# House_LED_Replace_WS5050.net
KiCad netlist of a schematic drawn in EAGLE
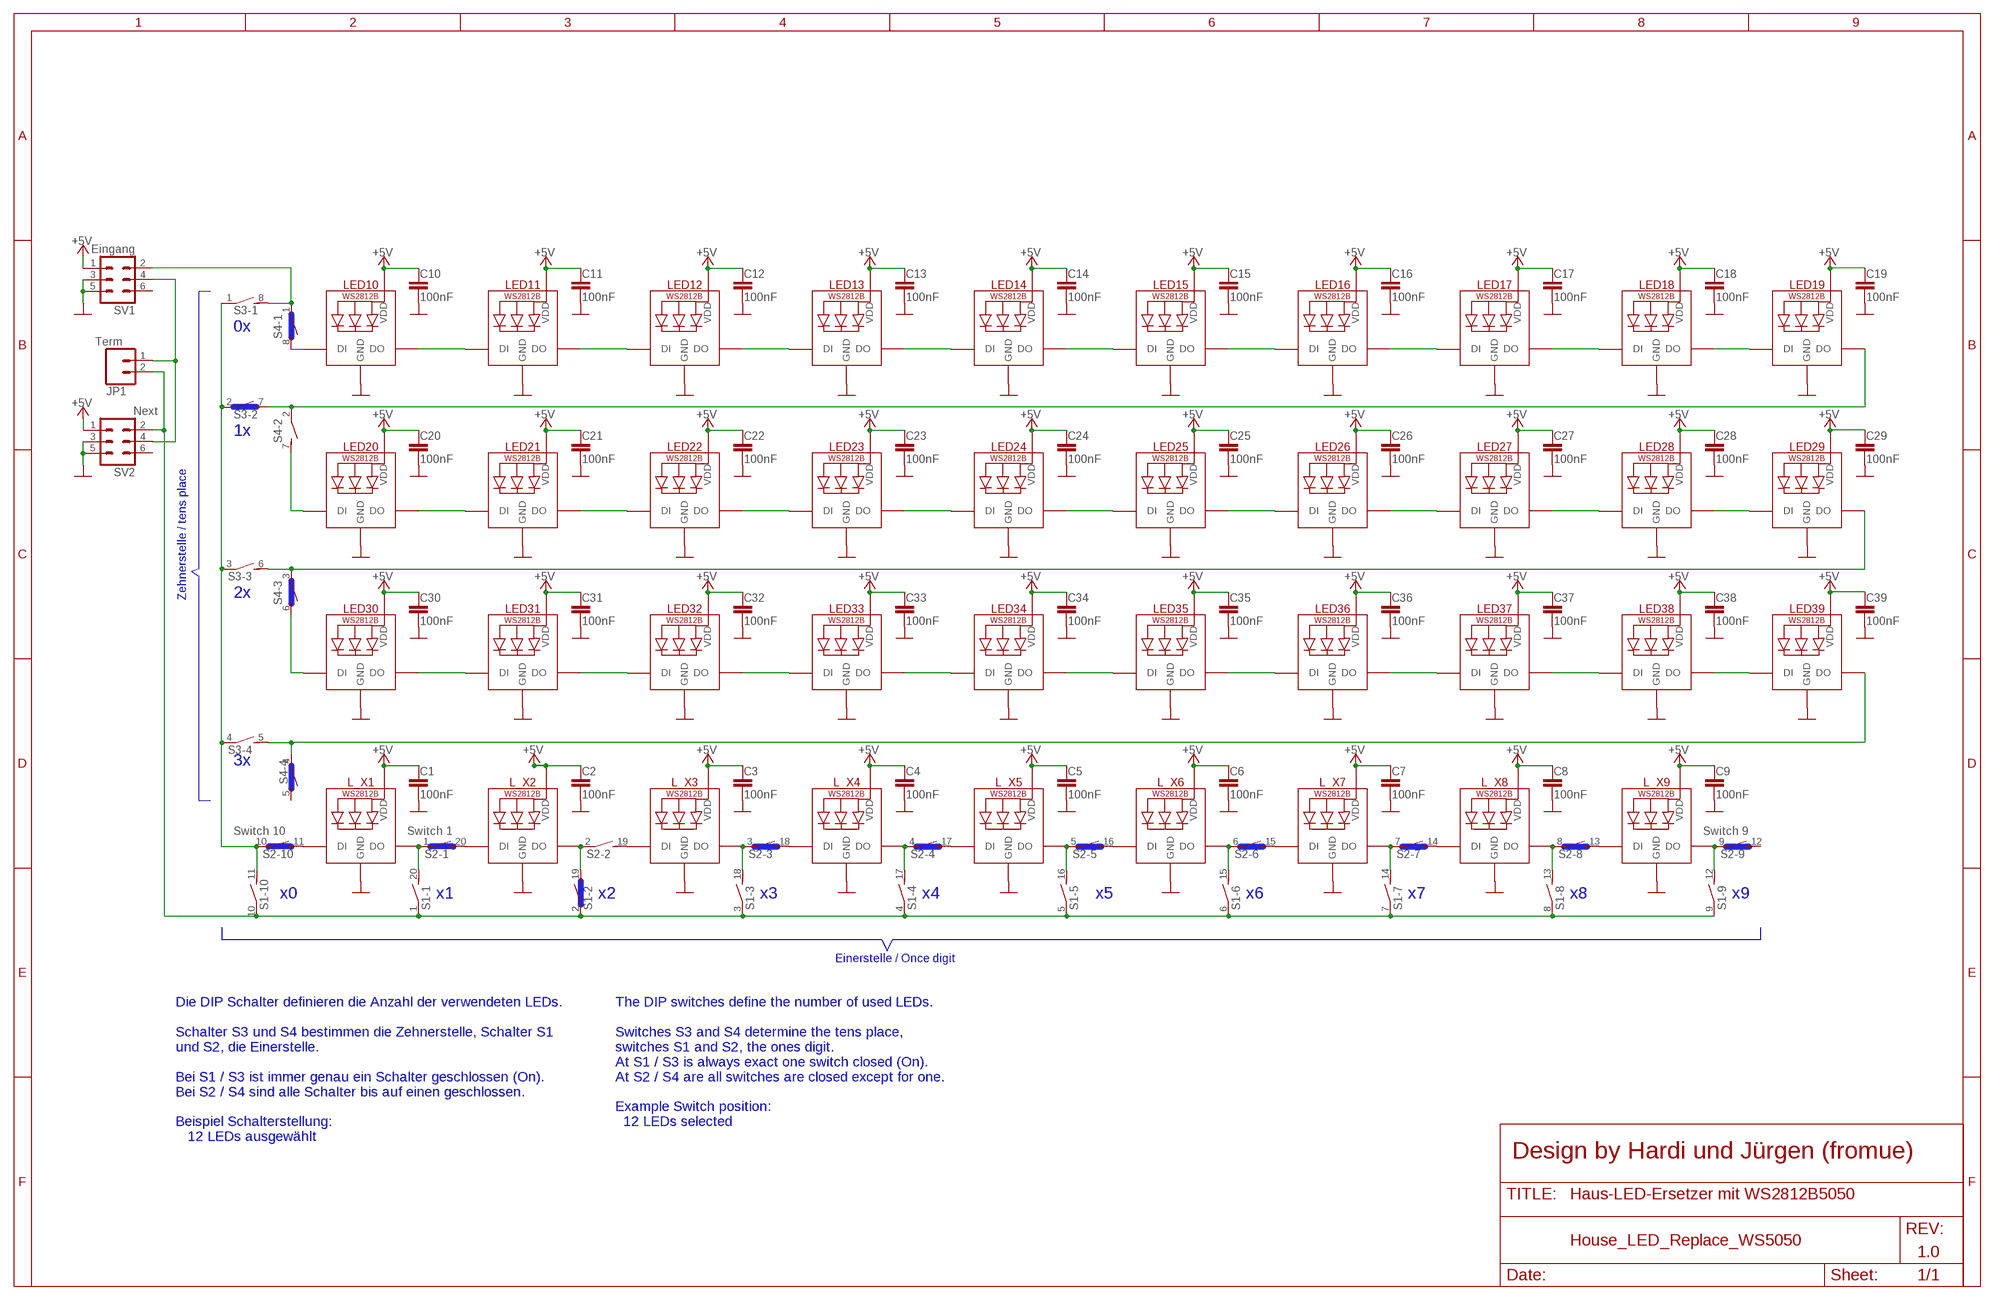
[diagram p0: schematic, sheet 1]

(export (version "E")
  (design (tool "Eeschema 10.0.6"))
  (components
    (comp (ref "C1")
      (value "100nF")
      (footprint "eagle-import:C0603")
      (libsource (lib "eagle-import") (part "C-EUC0603"))
    )
    (comp (ref "C2")
      (value "100nF")
      (footprint "eagle-import:C0603")
      (libsource (lib "eagle-import") (part "C-EUC0603"))
    )
    (comp (ref "C3")
      (value "100nF")
      (footprint "eagle-import:C0603")
      (libsource (lib "eagle-import") (part "C-EUC0603"))
    )
    (comp (ref "C4")
      (value "100nF")
      (footprint "eagle-import:C0603")
      (libsource (lib "eagle-import") (part "C-EUC0603"))
    )
    (comp (ref "C5")
      (value "100nF")
      (footprint "eagle-import:C0603")
      (libsource (lib "eagle-import") (part "C-EUC0603"))
    )
    (comp (ref "C6")
      (value "100nF")
      (footprint "eagle-import:C0603")
      (libsource (lib "eagle-import") (part "C-EUC0603"))
    )
    (comp (ref "C7")
      (value "100nF")
      (footprint "eagle-import:C0603")
      (libsource (lib "eagle-import") (part "C-EUC0603"))
    )
    (comp (ref "C8")
      (value "100nF")
      (footprint "eagle-import:C0603")
      (libsource (lib "eagle-import") (part "C-EUC0603"))
    )
    (comp (ref "C9")
      (value "100nF")
      (footprint "eagle-import:C0603")
      (libsource (lib "eagle-import") (part "C-EUC0603"))
    )
    (comp (ref "C10")
      (value "100nF")
      (footprint "eagle-import:C0603")
      (libsource (lib "eagle-import") (part "C-EUC0603"))
    )
    (comp (ref "C11")
      (value "100nF")
      (footprint "eagle-import:C0603")
      (libsource (lib "eagle-import") (part "C-EUC0603"))
    )
    (comp (ref "C12")
      (value "100nF")
      (footprint "eagle-import:C0603")
      (libsource (lib "eagle-import") (part "C-EUC0603"))
    )
    (comp (ref "C13")
      (value "100nF")
      (footprint "eagle-import:C0603")
      (libsource (lib "eagle-import") (part "C-EUC0603"))
    )
    (comp (ref "C14")
      (value "100nF")
      (footprint "eagle-import:C0603")
      (libsource (lib "eagle-import") (part "C-EUC0603"))
    )
    (comp (ref "C15")
      (value "100nF")
      (footprint "eagle-import:C0603")
      (libsource (lib "eagle-import") (part "C-EUC0603"))
    )
    (comp (ref "C16")
      (value "100nF")
      (footprint "eagle-import:C0603")
      (libsource (lib "eagle-import") (part "C-EUC0603"))
    )
    (comp (ref "C17")
      (value "100nF")
      (footprint "eagle-import:C0603")
      (libsource (lib "eagle-import") (part "C-EUC0603"))
    )
    (comp (ref "C18")
      (value "100nF")
      (footprint "eagle-import:C0603")
      (libsource (lib "eagle-import") (part "C-EUC0603"))
    )
    (comp (ref "C19")
      (value "100nF")
      (footprint "eagle-import:C0603")
      (libsource (lib "eagle-import") (part "C-EUC0603"))
    )
    (comp (ref "C20")
      (value "100nF")
      (footprint "eagle-import:C0603")
      (libsource (lib "eagle-import") (part "C-EUC0603"))
    )
    (comp (ref "C21")
      (value "100nF")
      (footprint "eagle-import:C0603")
      (libsource (lib "eagle-import") (part "C-EUC0603"))
    )
    (comp (ref "C22")
      (value "100nF")
      (footprint "eagle-import:C0603")
      (libsource (lib "eagle-import") (part "C-EUC0603"))
    )
    (comp (ref "C23")
      (value "100nF")
      (footprint "eagle-import:C0603")
      (libsource (lib "eagle-import") (part "C-EUC0603"))
    )
    (comp (ref "C24")
      (value "100nF")
      (footprint "eagle-import:C0603")
      (libsource (lib "eagle-import") (part "C-EUC0603"))
    )
    (comp (ref "C25")
      (value "100nF")
      (footprint "eagle-import:C0603")
      (libsource (lib "eagle-import") (part "C-EUC0603"))
    )
    (comp (ref "C26")
      (value "100nF")
      (footprint "eagle-import:C0603")
      (libsource (lib "eagle-import") (part "C-EUC0603"))
    )
    (comp (ref "C27")
      (value "100nF")
      (footprint "eagle-import:C0603")
      (libsource (lib "eagle-import") (part "C-EUC0603"))
    )
    (comp (ref "C28")
      (value "100nF")
      (footprint "eagle-import:C0603")
      (libsource (lib "eagle-import") (part "C-EUC0603"))
    )
    (comp (ref "C29")
      (value "100nF")
      (footprint "eagle-import:C0603")
      (libsource (lib "eagle-import") (part "C-EUC0603"))
    )
    (comp (ref "C30")
      (value "100nF")
      (footprint "eagle-import:C0603")
      (libsource (lib "eagle-import") (part "C-EUC0603"))
    )
    (comp (ref "C31")
      (value "100nF")
      (footprint "eagle-import:C0603")
      (libsource (lib "eagle-import") (part "C-EUC0603"))
    )
    (comp (ref "C32")
      (value "100nF")
      (footprint "eagle-import:C0603")
      (libsource (lib "eagle-import") (part "C-EUC0603"))
    )
    (comp (ref "C33")
      (value "100nF")
      (footprint "eagle-import:C0603")
      (libsource (lib "eagle-import") (part "C-EUC0603"))
    )
    (comp (ref "C34")
      (value "100nF")
      (footprint "eagle-import:C0603")
      (libsource (lib "eagle-import") (part "C-EUC0603"))
    )
    (comp (ref "C35")
      (value "100nF")
      (footprint "eagle-import:C0603")
      (libsource (lib "eagle-import") (part "C-EUC0603"))
    )
    (comp (ref "C36")
      (value "100nF")
      (footprint "eagle-import:C0603")
      (libsource (lib "eagle-import") (part "C-EUC0603"))
    )
    (comp (ref "C37")
      (value "100nF")
      (footprint "eagle-import:C0603")
      (libsource (lib "eagle-import") (part "C-EUC0603"))
    )
    (comp (ref "C38")
      (value "100nF")
      (footprint "eagle-import:C0603")
      (libsource (lib "eagle-import") (part "C-EUC0603"))
    )
    (comp (ref "C39")
      (value "100nF")
      (footprint "eagle-import:C0603")
      (libsource (lib "eagle-import") (part "C-EUC0603"))
    )
    (comp (ref "JP1")
      (value "Term")
      (footprint "eagle-import:1X02")
      (libsource (lib "eagle-import") (part "M02PTH"))
    )
    (comp (ref "LED10")
      (value "WS2812B5050")
      (footprint "eagle-import:WS2812B")
      (libsource (lib "eagle-import") (part "WS2812B5050"))
    )
    (comp (ref "LED11")
      (value "WS2812B5050")
      (footprint "eagle-import:WS2812B")
      (libsource (lib "eagle-import") (part "WS2812B5050"))
    )
    (comp (ref "LED12")
      (value "WS2812B5050")
      (footprint "eagle-import:WS2812B")
      (libsource (lib "eagle-import") (part "WS2812B5050"))
    )
    (comp (ref "LED13")
      (value "WS2812B5050")
      (footprint "eagle-import:WS2812B")
      (libsource (lib "eagle-import") (part "WS2812B5050"))
    )
    (comp (ref "LED14")
      (value "WS2812B5050")
      (footprint "eagle-import:WS2812B")
      (libsource (lib "eagle-import") (part "WS2812B5050"))
    )
    (comp (ref "LED15")
      (value "WS2812B5050")
      (footprint "eagle-import:WS2812B")
      (libsource (lib "eagle-import") (part "WS2812B5050"))
    )
    (comp (ref "LED16")
      (value "WS2812B5050")
      (footprint "eagle-import:WS2812B")
      (libsource (lib "eagle-import") (part "WS2812B5050"))
    )
    (comp (ref "LED17")
      (value "WS2812B5050")
      (footprint "eagle-import:WS2812B")
      (libsource (lib "eagle-import") (part "WS2812B5050"))
    )
    (comp (ref "LED18")
      (value "WS2812B5050")
      (footprint "eagle-import:WS2812B")
      (libsource (lib "eagle-import") (part "WS2812B5050"))
    )
    (comp (ref "LED19")
      (value "WS2812B5050")
      (footprint "eagle-import:WS2812B")
      (libsource (lib "eagle-import") (part "WS2812B5050"))
    )
    (comp (ref "LED20")
      (value "WS2812B5050")
      (footprint "eagle-import:WS2812B")
      (libsource (lib "eagle-import") (part "WS2812B5050"))
    )
    (comp (ref "LED21")
      (value "WS2812B5050")
      (footprint "eagle-import:WS2812B")
      (libsource (lib "eagle-import") (part "WS2812B5050"))
    )
    (comp (ref "LED22")
      (value "WS2812B5050")
      (footprint "eagle-import:WS2812B")
      (libsource (lib "eagle-import") (part "WS2812B5050"))
    )
    (comp (ref "LED23")
      (value "WS2812B5050")
      (footprint "eagle-import:WS2812B")
      (libsource (lib "eagle-import") (part "WS2812B5050"))
    )
    (comp (ref "LED24")
      (value "WS2812B5050")
      (footprint "eagle-import:WS2812B")
      (libsource (lib "eagle-import") (part "WS2812B5050"))
    )
    (comp (ref "LED25")
      (value "WS2812B5050")
      (footprint "eagle-import:WS2812B")
      (libsource (lib "eagle-import") (part "WS2812B5050"))
    )
    (comp (ref "LED26")
      (value "WS2812B5050")
      (footprint "eagle-import:WS2812B")
      (libsource (lib "eagle-import") (part "WS2812B5050"))
    )
    (comp (ref "LED27")
      (value "WS2812B5050")
      (footprint "eagle-import:WS2812B")
      (libsource (lib "eagle-import") (part "WS2812B5050"))
    )
    (comp (ref "LED28")
      (value "WS2812B5050")
      (footprint "eagle-import:WS2812B")
      (libsource (lib "eagle-import") (part "WS2812B5050"))
    )
    (comp (ref "LED29")
      (value "WS2812B5050")
      (footprint "eagle-import:WS2812B")
      (libsource (lib "eagle-import") (part "WS2812B5050"))
    )
    (comp (ref "LED30")
      (value "WS2812B5050")
      (footprint "eagle-import:WS2812B")
      (libsource (lib "eagle-import") (part "WS2812B5050"))
    )
    (comp (ref "LED31")
      (value "WS2812B5050")
      (footprint "eagle-import:WS2812B")
      (libsource (lib "eagle-import") (part "WS2812B5050"))
    )
    (comp (ref "LED32")
      (value "WS2812B5050")
      (footprint "eagle-import:WS2812B")
      (libsource (lib "eagle-import") (part "WS2812B5050"))
    )
    (comp (ref "LED33")
      (value "WS2812B5050")
      (footprint "eagle-import:WS2812B")
      (libsource (lib "eagle-import") (part "WS2812B5050"))
    )
    (comp (ref "LED34")
      (value "WS2812B5050")
      (footprint "eagle-import:WS2812B")
      (libsource (lib "eagle-import") (part "WS2812B5050"))
    )
    (comp (ref "LED35")
      (value "WS2812B5050")
      (footprint "eagle-import:WS2812B")
      (libsource (lib "eagle-import") (part "WS2812B5050"))
    )
    (comp (ref "LED36")
      (value "WS2812B5050")
      (footprint "eagle-import:WS2812B")
      (libsource (lib "eagle-import") (part "WS2812B5050"))
    )
    (comp (ref "LED37")
      (value "WS2812B5050")
      (footprint "eagle-import:WS2812B")
      (libsource (lib "eagle-import") (part "WS2812B5050"))
    )
    (comp (ref "LED38")
      (value "WS2812B5050")
      (footprint "eagle-import:WS2812B")
      (libsource (lib "eagle-import") (part "WS2812B5050"))
    )
    (comp (ref "LED39")
      (value "WS2812B5050")
      (footprint "eagle-import:WS2812B")
      (libsource (lib "eagle-import") (part "WS2812B5050"))
    )
    (comp (ref "L_X1")
      (value "WS2812B5050")
      (footprint "eagle-import:WS2812B")
      (libsource (lib "eagle-import") (part "WS2812B5050"))
    )
    (comp (ref "L_X2")
      (value "WS2812B5050")
      (footprint "eagle-import:WS2812B")
      (libsource (lib "eagle-import") (part "WS2812B5050"))
    )
    (comp (ref "L_X3")
      (value "WS2812B5050")
      (footprint "eagle-import:WS2812B")
      (libsource (lib "eagle-import") (part "WS2812B5050"))
    )
    (comp (ref "L_X4")
      (value "WS2812B5050")
      (footprint "eagle-import:WS2812B")
      (libsource (lib "eagle-import") (part "WS2812B5050"))
    )
    (comp (ref "L_X5")
      (value "WS2812B5050")
      (footprint "eagle-import:WS2812B")
      (libsource (lib "eagle-import") (part "WS2812B5050"))
    )
    (comp (ref "L_X6")
      (value "WS2812B5050")
      (footprint "eagle-import:WS2812B")
      (libsource (lib "eagle-import") (part "WS2812B5050"))
    )
    (comp (ref "L_X7")
      (value "WS2812B5050")
      (footprint "eagle-import:WS2812B")
      (libsource (lib "eagle-import") (part "WS2812B5050"))
    )
    (comp (ref "L_X8")
      (value "WS2812B5050")
      (footprint "eagle-import:WS2812B")
      (libsource (lib "eagle-import") (part "WS2812B5050"))
    )
    (comp (ref "L_X9")
      (value "WS2812B5050")
      (footprint "eagle-import:WS2812B")
      (libsource (lib "eagle-import") (part "WS2812B5050"))
    )
    (comp (ref "S1")
      (value "DIP10SB")
      (footprint "eagle-import:DIP10SB")
      (libsource (lib "eagle-import") (part "DIP10SB"))
    )
    (comp (ref "S2")
      (value "DIP10SB")
      (footprint "eagle-import:DIP10SB")
      (libsource (lib "eagle-import") (part "DIP10SB"))
    )
    (comp (ref "S3")
      (value "DIP04S")
      (footprint "eagle-import:DIP04S")
      (libsource (lib "eagle-import") (part "DIP04S"))
    )
    (comp (ref "S4")
      (value "DIP04S")
      (footprint "eagle-import:DIP04S")
      (libsource (lib "eagle-import") (part "DIP04S"))
    )
    (comp (ref "SV1")
      (value "Eingang")
      (footprint "eagle-import:ML6")
      (libsource (lib "eagle-import") (part "ML6"))
    )
    (comp (ref "SV2")
      (value "Next")
      (footprint "eagle-import:ML6")
      (libsource (lib "eagle-import") (part "ML6"))
    )
  )
  (nets
    (net (code "1") (name "+5V") (class "Default")
      (node (ref "C1") (pin "1") (pinfunction "1_1") (pintype "passive"))
      (node (ref "C10") (pin "1") (pinfunction "1_1") (pintype "passive"))
      (node (ref "C11") (pin "1") (pinfunction "1_1") (pintype "passive"))
      (node (ref "C12") (pin "1") (pinfunction "1_1") (pintype "passive"))
      (node (ref "C13") (pin "1") (pinfunction "1_1") (pintype "passive"))
      (node (ref "C14") (pin "1") (pinfunction "1_1") (pintype "passive"))
      (node (ref "C15") (pin "1") (pinfunction "1_1") (pintype "passive"))
      (node (ref "C16") (pin "1") (pinfunction "1_1") (pintype "passive"))
      (node (ref "C17") (pin "1") (pinfunction "1_1") (pintype "passive"))
      (node (ref "C18") (pin "1") (pinfunction "1_1") (pintype "passive"))
      (node (ref "C19") (pin "1") (pinfunction "1_1") (pintype "passive"))
      (node (ref "C2") (pin "1") (pinfunction "1_1") (pintype "passive"))
      (node (ref "C20") (pin "1") (pinfunction "1_1") (pintype "passive"))
      (node (ref "C21") (pin "1") (pinfunction "1_1") (pintype "passive"))
      (node (ref "C22") (pin "1") (pinfunction "1_1") (pintype "passive"))
      (node (ref "C23") (pin "1") (pinfunction "1_1") (pintype "passive"))
      (node (ref "C24") (pin "1") (pinfunction "1_1") (pintype "passive"))
      (node (ref "C25") (pin "1") (pinfunction "1_1") (pintype "passive"))
      (node (ref "C26") (pin "1") (pinfunction "1_1") (pintype "passive"))
      (node (ref "C27") (pin "1") (pinfunction "1_1") (pintype "passive"))
      (node (ref "C28") (pin "1") (pinfunction "1_1") (pintype "passive"))
      (node (ref "C29") (pin "1") (pinfunction "1_1") (pintype "passive"))
      (node (ref "C3") (pin "1") (pinfunction "1_1") (pintype "passive"))
      (node (ref "C30") (pin "1") (pinfunction "1_1") (pintype "passive"))
      (node (ref "C31") (pin "1") (pinfunction "1_1") (pintype "passive"))
      (node (ref "C32") (pin "1") (pinfunction "1_1") (pintype "passive"))
      (node (ref "C33") (pin "1") (pinfunction "1_1") (pintype "passive"))
      (node (ref "C34") (pin "1") (pinfunction "1_1") (pintype "passive"))
      (node (ref "C35") (pin "1") (pinfunction "1_1") (pintype "passive"))
      (node (ref "C36") (pin "1") (pinfunction "1_1") (pintype "passive"))
      (node (ref "C37") (pin "1") (pinfunction "1_1") (pintype "passive"))
      (node (ref "C38") (pin "1") (pinfunction "1_1") (pintype "passive"))
      (node (ref "C39") (pin "1") (pinfunction "1_1") (pintype "passive"))
      (node (ref "C4") (pin "1") (pinfunction "1_1") (pintype "passive"))
      (node (ref "C5") (pin "1") (pinfunction "1_1") (pintype "passive"))
      (node (ref "C6") (pin "1") (pinfunction "1_1") (pintype "passive"))
      (node (ref "C7") (pin "1") (pinfunction "1_1") (pintype "passive"))
      (node (ref "C8") (pin "1") (pinfunction "1_1") (pintype "passive"))
      (node (ref "C9") (pin "1") (pinfunction "1_1") (pintype "passive"))
      (node (ref "LED10") (pin "1-5V") (pinfunction "VDD_1-5V") (pintype "power_in"))
      (node (ref "LED11") (pin "1-5V") (pinfunction "VDD_1-5V") (pintype "power_in"))
      (node (ref "LED12") (pin "1-5V") (pinfunction "VDD_1-5V") (pintype "power_in"))
      (node (ref "LED13") (pin "1-5V") (pinfunction "VDD_1-5V") (pintype "power_in"))
      (node (ref "LED14") (pin "1-5V") (pinfunction "VDD_1-5V") (pintype "power_in"))
      (node (ref "LED15") (pin "1-5V") (pinfunction "VDD_1-5V") (pintype "power_in"))
      (node (ref "LED16") (pin "1-5V") (pinfunction "VDD_1-5V") (pintype "power_in"))
      (node (ref "LED17") (pin "1-5V") (pinfunction "VDD_1-5V") (pintype "power_in"))
      (node (ref "LED18") (pin "1-5V") (pinfunction "VDD_1-5V") (pintype "power_in"))
      (node (ref "LED19") (pin "1-5V") (pinfunction "VDD_1-5V") (pintype "power_in"))
      (node (ref "LED20") (pin "1-5V") (pinfunction "VDD_1-5V") (pintype "power_in"))
      (node (ref "LED21") (pin "1-5V") (pinfunction "VDD_1-5V") (pintype "power_in"))
      (node (ref "LED22") (pin "1-5V") (pinfunction "VDD_1-5V") (pintype "power_in"))
      (node (ref "LED23") (pin "1-5V") (pinfunction "VDD_1-5V") (pintype "power_in"))
      (node (ref "LED24") (pin "1-5V") (pinfunction "VDD_1-5V") (pintype "power_in"))
      (node (ref "LED25") (pin "1-5V") (pinfunction "VDD_1-5V") (pintype "power_in"))
      (node (ref "LED26") (pin "1-5V") (pinfunction "VDD_1-5V") (pintype "power_in"))
      (node (ref "LED27") (pin "1-5V") (pinfunction "VDD_1-5V") (pintype "power_in"))
      (node (ref "LED28") (pin "1-5V") (pinfunction "VDD_1-5V") (pintype "power_in"))
      (node (ref "LED29") (pin "1-5V") (pinfunction "VDD_1-5V") (pintype "power_in"))
      (node (ref "LED30") (pin "1-5V") (pinfunction "VDD_1-5V") (pintype "power_in"))
      (node (ref "LED31") (pin "1-5V") (pinfunction "VDD_1-5V") (pintype "power_in"))
      (node (ref "LED32") (pin "1-5V") (pinfunction "VDD_1-5V") (pintype "power_in"))
      (node (ref "LED33") (pin "1-5V") (pinfunction "VDD_1-5V") (pintype "power_in"))
      (node (ref "LED34") (pin "1-5V") (pinfunction "VDD_1-5V") (pintype "power_in"))
      (node (ref "LED35") (pin "1-5V") (pinfunction "VDD_1-5V") (pintype "power_in"))
      (node (ref "LED36") (pin "1-5V") (pinfunction "VDD_1-5V") (pintype "power_in"))
      (node (ref "LED37") (pin "1-5V") (pinfunction "VDD_1-5V") (pintype "power_in"))
      (node (ref "LED38") (pin "1-5V") (pinfunction "VDD_1-5V") (pintype "power_in"))
      (node (ref "LED39") (pin "1-5V") (pinfunction "VDD_1-5V") (pintype "power_in"))
      (node (ref "L_X1") (pin "1-5V") (pinfunction "VDD_1-5V") (pintype "power_in"))
      (node (ref "L_X2") (pin "1-5V") (pinfunction "VDD_1-5V") (pintype "power_in"))
      (node (ref "L_X3") (pin "1-5V") (pinfunction "VDD_1-5V") (pintype "power_in"))
      (node (ref "L_X4") (pin "1-5V") (pinfunction "VDD_1-5V") (pintype "power_in"))
      (node (ref "L_X5") (pin "1-5V") (pinfunction "VDD_1-5V") (pintype "power_in"))
      (node (ref "L_X6") (pin "1-5V") (pinfunction "VDD_1-5V") (pintype "power_in"))
      (node (ref "L_X7") (pin "1-5V") (pinfunction "VDD_1-5V") (pintype "power_in"))
      (node (ref "L_X8") (pin "1-5V") (pinfunction "VDD_1-5V") (pintype "power_in"))
      (node (ref "L_X9") (pin "1-5V") (pinfunction "VDD_1-5V") (pintype "power_in"))
      (node (ref "SV1") (pin "1") (pinfunction "1_1") (pintype "passive"))
      (node (ref "SV2") (pin "1") (pinfunction "1_1") (pintype "passive"))
    )
    (net (code "2") (name "GND") (class "Default")
      (node (ref "C1") (pin "2") (pinfunction "2_2") (pintype "passive"))
      (node (ref "C10") (pin "2") (pinfunction "2_2") (pintype "passive"))
      (node (ref "C11") (pin "2") (pinfunction "2_2") (pintype "passive"))
      (node (ref "C12") (pin "2") (pinfunction "2_2") (pintype "passive"))
      (node (ref "C13") (pin "2") (pinfunction "2_2") (pintype "passive"))
      (node (ref "C14") (pin "2") (pinfunction "2_2") (pintype "passive"))
      (node (ref "C15") (pin "2") (pinfunction "2_2") (pintype "passive"))
      (node (ref "C16") (pin "2") (pinfunction "2_2") (pintype "passive"))
      (node (ref "C17") (pin "2") (pinfunction "2_2") (pintype "passive"))
      (node (ref "C18") (pin "2") (pinfunction "2_2") (pintype "passive"))
      (node (ref "C19") (pin "2") (pinfunction "2_2") (pintype "passive"))
      (node (ref "C2") (pin "2") (pinfunction "2_2") (pintype "passive"))
      (node (ref "C20") (pin "2") (pinfunction "2_2") (pintype "passive"))
      (node (ref "C21") (pin "2") (pinfunction "2_2") (pintype "passive"))
      (node (ref "C22") (pin "2") (pinfunction "2_2") (pintype "passive"))
      (node (ref "C23") (pin "2") (pinfunction "2_2") (pintype "passive"))
      (node (ref "C24") (pin "2") (pinfunction "2_2") (pintype "passive"))
      (node (ref "C25") (pin "2") (pinfunction "2_2") (pintype "passive"))
      (node (ref "C26") (pin "2") (pinfunction "2_2") (pintype "passive"))
      (node (ref "C27") (pin "2") (pinfunction "2_2") (pintype "passive"))
      (node (ref "C28") (pin "2") (pinfunction "2_2") (pintype "passive"))
      (node (ref "C29") (pin "2") (pinfunction "2_2") (pintype "passive"))
      (node (ref "C3") (pin "2") (pinfunction "2_2") (pintype "passive"))
      (node (ref "C30") (pin "2") (pinfunction "2_2") (pintype "passive"))
      (node (ref "C31") (pin "2") (pinfunction "2_2") (pintype "passive"))
      (node (ref "C32") (pin "2") (pinfunction "2_2") (pintype "passive"))
      (node (ref "C33") (pin "2") (pinfunction "2_2") (pintype "passive"))
      (node (ref "C34") (pin "2") (pinfunction "2_2") (pintype "passive"))
      (node (ref "C35") (pin "2") (pinfunction "2_2") (pintype "passive"))
      (node (ref "C36") (pin "2") (pinfunction "2_2") (pintype "passive"))
      (node (ref "C37") (pin "2") (pinfunction "2_2") (pintype "passive"))
      (node (ref "C38") (pin "2") (pinfunction "2_2") (pintype "passive"))
      (node (ref "C39") (pin "2") (pinfunction "2_2") (pintype "passive"))
      (node (ref "C4") (pin "2") (pinfunction "2_2") (pintype "passive"))
      (node (ref "C5") (pin "2") (pinfunction "2_2") (pintype "passive"))
      (node (ref "C6") (pin "2") (pinfunction "2_2") (pintype "passive"))
      (node (ref "C7") (pin "2") (pinfunction "2_2") (pintype "passive"))
      (node (ref "C8") (pin "2") (pinfunction "2_2") (pintype "passive"))
      (node (ref "C9") (pin "2") (pinfunction "2_2") (pintype "passive"))
      (node (ref "LED10") (pin "3-GND") (pinfunction "GND_3-GND") (pintype "power_in"))
      (node (ref "LED11") (pin "3-GND") (pinfunction "GND_3-GND") (pintype "power_in"))
      (node (ref "LED12") (pin "3-GND") (pinfunction "GND_3-GND") (pintype "power_in"))
      (node (ref "LED13") (pin "3-GND") (pinfunction "GND_3-GND") (pintype "power_in"))
      (node (ref "LED14") (pin "3-GND") (pinfunction "GND_3-GND") (pintype "power_in"))
      (node (ref "LED15") (pin "3-GND") (pinfunction "GND_3-GND") (pintype "power_in"))
      (node (ref "LED16") (pin "3-GND") (pinfunction "GND_3-GND") (pintype "power_in"))
      (node (ref "LED17") (pin "3-GND") (pinfunction "GND_3-GND") (pintype "power_in"))
      (node (ref "LED18") (pin "3-GND") (pinfunction "GND_3-GND") (pintype "power_in"))
      (node (ref "LED19") (pin "3-GND") (pinfunction "GND_3-GND") (pintype "power_in"))
      (node (ref "LED20") (pin "3-GND") (pinfunction "GND_3-GND") (pintype "power_in"))
      (node (ref "LED21") (pin "3-GND") (pinfunction "GND_3-GND") (pintype "power_in"))
      (node (ref "LED22") (pin "3-GND") (pinfunction "GND_3-GND") (pintype "power_in"))
      (node (ref "LED23") (pin "3-GND") (pinfunction "GND_3-GND") (pintype "power_in"))
      (node (ref "LED24") (pin "3-GND") (pinfunction "GND_3-GND") (pintype "power_in"))
      (node (ref "LED25") (pin "3-GND") (pinfunction "GND_3-GND") (pintype "power_in"))
      (node (ref "LED26") (pin "3-GND") (pinfunction "GND_3-GND") (pintype "power_in"))
      (node (ref "LED27") (pin "3-GND") (pinfunction "GND_3-GND") (pintype "power_in"))
      (node (ref "LED28") (pin "3-GND") (pinfunction "GND_3-GND") (pintype "power_in"))
      (node (ref "LED29") (pin "3-GND") (pinfunction "GND_3-GND") (pintype "power_in"))
      (node (ref "LED30") (pin "3-GND") (pinfunction "GND_3-GND") (pintype "power_in"))
      (node (ref "LED31") (pin "3-GND") (pinfunction "GND_3-GND") (pintype "power_in"))
      (node (ref "LED32") (pin "3-GND") (pinfunction "GND_3-GND") (pintype "power_in"))
      (node (ref "LED33") (pin "3-GND") (pinfunction "GND_3-GND") (pintype "power_in"))
      (node (ref "LED34") (pin "3-GND") (pinfunction "GND_3-GND") (pintype "power_in"))
      (node (ref "LED35") (pin "3-GND") (pinfunction "GND_3-GND") (pintype "power_in"))
      (node (ref "LED36") (pin "3-GND") (pinfunction "GND_3-GND") (pintype "power_in"))
      (node (ref "LED37") (pin "3-GND") (pinfunction "GND_3-GND") (pintype "power_in"))
      (node (ref "LED38") (pin "3-GND") (pinfunction "GND_3-GND") (pintype "power_in"))
      (node (ref "LED39") (pin "3-GND") (pinfunction "GND_3-GND") (pintype "power_in"))
      (node (ref "L_X1") (pin "3-GND") (pinfunction "GND_3-GND") (pintype "power_in"))
      (node (ref "L_X2") (pin "3-GND") (pinfunction "GND_3-GND") (pintype "power_in"))
      (node (ref "L_X3") (pin "3-GND") (pinfunction "GND_3-GND") (pintype "power_in"))
      (node (ref "L_X4") (pin "3-GND") (pinfunction "GND_3-GND") (pintype "power_in"))
      (node (ref "L_X5") (pin "3-GND") (pinfunction "GND_3-GND") (pintype "power_in"))
      (node (ref "L_X6") (pin "3-GND") (pinfunction "GND_3-GND") (pintype "power_in"))
      (node (ref "L_X7") (pin "3-GND") (pinfunction "GND_3-GND") (pintype "power_in"))
      (node (ref "L_X8") (pin "3-GND") (pinfunction "GND_3-GND") (pintype "power_in"))
      (node (ref "L_X9") (pin "3-GND") (pinfunction "GND_3-GND") (pintype "power_in"))
      (node (ref "SV1") (pin "3") (pinfunction "3_3") (pintype "passive"))
      (node (ref "SV1") (pin "5") (pinfunction "5_5") (pintype "passive"))
      (node (ref "SV2") (pin "3") (pinfunction "3_3") (pintype "passive"))
      (node (ref "SV2") (pin "5") (pinfunction "5_5") (pintype "passive"))
    )
    (net (code "3") (name "Net-(JP1-Pad1)") (class "Default")
      (node (ref "JP1") (pin "1") (pinfunction "1_1") (pintype "passive"))
      (node (ref "SV1") (pin "4") (pinfunction "4_4") (pintype "passive"))
      (node (ref "SV2") (pin "4") (pinfunction "4_4") (pintype "passive"))
    )
    (net (code "4") (name "Net-(LED10-DI)") (class "Default")
      (node (ref "LED10") (pin "4-DIN") (pinfunction "DI_4-DIN") (pintype "input"))
      (node (ref "S4") (pin "8") (pinfunction "2_8") (pintype "passive"))
    )
    (net (code "5") (name "Net-(LED10-DO)") (class "Default")
      (node (ref "LED10") (pin "2-DOUT") (pinfunction "DO_2-DOUT") (pintype "output"))
      (node (ref "LED11") (pin "4-DIN") (pinfunction "DI_4-DIN") (pintype "input"))
    )
    (net (code "6") (name "Net-(LED11-DO)") (class "Default")
      (node (ref "LED11") (pin "2-DOUT") (pinfunction "DO_2-DOUT") (pintype "output"))
      (node (ref "LED12") (pin "4-DIN") (pinfunction "DI_4-DIN") (pintype "input"))
    )
    (net (code "7") (name "Net-(LED12-DO)") (class "Default")
      (node (ref "LED12") (pin "2-DOUT") (pinfunction "DO_2-DOUT") (pintype "output"))
      (node (ref "LED13") (pin "4-DIN") (pinfunction "DI_4-DIN") (pintype "input"))
    )
    (net (code "8") (name "Net-(LED13-DO)") (class "Default")
      (node (ref "LED13") (pin "2-DOUT") (pinfunction "DO_2-DOUT") (pintype "output"))
      (node (ref "LED14") (pin "4-DIN") (pinfunction "DI_4-DIN") (pintype "input"))
    )
    (net (code "9") (name "Net-(LED14-DO)") (class "Default")
      (node (ref "LED14") (pin "2-DOUT") (pinfunction "DO_2-DOUT") (pintype "output"))
      (node (ref "LED15") (pin "4-DIN") (pinfunction "DI_4-DIN") (pintype "input"))
    )
    (net (code "10") (name "Net-(LED15-DO)") (class "Default")
      (node (ref "LED15") (pin "2-DOUT") (pinfunction "DO_2-DOUT") (pintype "output"))
      (node (ref "LED16") (pin "4-DIN") (pinfunction "DI_4-DIN") (pintype "input"))
    )
    (net (code "11") (name "Net-(LED16-DO)") (class "Default")
      (node (ref "LED16") (pin "2-DOUT") (pinfunction "DO_2-DOUT") (pintype "output"))
      (node (ref "LED17") (pin "4-DIN") (pinfunction "DI_4-DIN") (pintype "input"))
    )
    (net (code "12") (name "Net-(LED17-DO)") (class "Default")
      (node (ref "LED17") (pin "2-DOUT") (pinfunction "DO_2-DOUT") (pintype "output"))
      (node (ref "LED18") (pin "4-DIN") (pinfunction "DI_4-DIN") (pintype "input"))
    )
    (net (code "13") (name "Net-(LED18-DO)") (class "Default")
      (node (ref "LED18") (pin "2-DOUT") (pinfunction "DO_2-DOUT") (pintype "output"))
      (node (ref "LED19") (pin "4-DIN") (pinfunction "DI_4-DIN") (pintype "input"))
    )
    (net (code "14") (name "Net-(LED19-DO)") (class "Default")
      (node (ref "LED19") (pin "2-DOUT") (pinfunction "DO_2-DOUT") (pintype "output"))
      (node (ref "S3") (pin "7") (pinfunction "2_7") (pintype "passive"))
      (node (ref "S4") (pin "2") (pinfunction "1_2") (pintype "passive"))
    )
    (net (code "15") (name "Net-(LED20-DI)") (class "Default")
      (node (ref "LED20") (pin "4-DIN") (pinfunction "DI_4-DIN") (pintype "input"))
      (node (ref "S4") (pin "7") (pinfunction "2_7") (pintype "passive"))
    )
    (net (code "16") (name "Net-(LED20-DO)") (class "Default")
      (node (ref "LED20") (pin "2-DOUT") (pinfunction "DO_2-DOUT") (pintype "output"))
      (node (ref "LED21") (pin "4-DIN") (pinfunction "DI_4-DIN") (pintype "input"))
    )
    (net (code "17") (name "Net-(LED21-DO)") (class "Default")
      (node (ref "LED21") (pin "2-DOUT") (pinfunction "DO_2-DOUT") (pintype "output"))
      (node (ref "LED22") (pin "4-DIN") (pinfunction "DI_4-DIN") (pintype "input"))
    )
    (net (code "18") (name "Net-(LED22-DO)") (class "Default")
      (node (ref "LED22") (pin "2-DOUT") (pinfunction "DO_2-DOUT") (pintype "output"))
      (node (ref "LED23") (pin "4-DIN") (pinfunction "DI_4-DIN") (pintype "input"))
    )
    (net (code "19") (name "Net-(LED23-DO)") (class "Default")
      (node (ref "LED23") (pin "2-DOUT") (pinfunction "DO_2-DOUT") (pintype "output"))
      (node (ref "LED24") (pin "4-DIN") (pinfunction "DI_4-DIN") (pintype "input"))
    )
    (net (code "20") (name "Net-(LED24-DO)") (class "Default")
      (node (ref "LED24") (pin "2-DOUT") (pinfunction "DO_2-DOUT") (pintype "output"))
      (node (ref "LED25") (pin "4-DIN") (pinfunction "DI_4-DIN") (pintype "input"))
    )
    (net (code "21") (name "Net-(LED25-DO)") (class "Default")
      (node (ref "LED25") (pin "2-DOUT") (pinfunction "DO_2-DOUT") (pintype "output"))
      (node (ref "LED26") (pin "4-DIN") (pinfunction "DI_4-DIN") (pintype "input"))
    )
    (net (code "22") (name "Net-(LED26-DO)") (class "Default")
      (node (ref "LED26") (pin "2-DOUT") (pinfunction "DO_2-DOUT") (pintype "output"))
      (node (ref "LED27") (pin "4-DIN") (pinfunction "DI_4-DIN") (pintype "input"))
    )
    (net (code "23") (name "Net-(LED27-DO)") (class "Default")
      (node (ref "LED27") (pin "2-DOUT") (pinfunction "DO_2-DOUT") (pintype "output"))
      (node (ref "LED28") (pin "4-DIN") (pinfunction "DI_4-DIN") (pintype "input"))
    )
    (net (code "24") (name "Net-(LED28-DO)") (class "Default")
      (node (ref "LED28") (pin "2-DOUT") (pinfunction "DO_2-DOUT") (pintype "output"))
      (node (ref "LED29") (pin "4-DIN") (pinfunction "DI_4-DIN") (pintype "input"))
    )
    (net (code "25") (name "Net-(LED29-DO)") (class "Default")
      (node (ref "LED29") (pin "2-DOUT") (pinfunction "DO_2-DOUT") (pintype "output"))
      (node (ref "S3") (pin "6") (pinfunction "2_6") (pintype "passive"))
      (node (ref "S4") (pin "3") (pinfunction "1_3") (pintype "passive"))
    )
    (net (code "26") (name "Net-(LED30-DI)") (class "Default")
      (node (ref "LED30") (pin "4-DIN") (pinfunction "DI_4-DIN") (pintype "input"))
      (node (ref "S4") (pin "6") (pinfunction "2_6") (pintype "passive"))
    )
    (net (code "27") (name "Net-(LED30-DO)") (class "Default")
      (node (ref "LED30") (pin "2-DOUT") (pinfunction "DO_2-DOUT") (pintype "output"))
      (node (ref "LED31") (pin "4-DIN") (pinfunction "DI_4-DIN") (pintype "input"))
    )
    (net (code "28") (name "Net-(LED31-DO)") (class "Default")
      (node (ref "LED31") (pin "2-DOUT") (pinfunction "DO_2-DOUT") (pintype "output"))
      (node (ref "LED32") (pin "4-DIN") (pinfunction "DI_4-DIN") (pintype "input"))
    )
    (net (code "29") (name "Net-(LED32-DO)") (class "Default")
      (node (ref "LED32") (pin "2-DOUT") (pinfunction "DO_2-DOUT") (pintype "output"))
      (node (ref "LED33") (pin "4-DIN") (pinfunction "DI_4-DIN") (pintype "input"))
    )
    (net (code "30") (name "Net-(LED33-DO)") (class "Default")
      (node (ref "LED33") (pin "2-DOUT") (pinfunction "DO_2-DOUT") (pintype "output"))
      (node (ref "LED34") (pin "4-DIN") (pinfunction "DI_4-DIN") (pintype "input"))
    )
    (net (code "31") (name "Net-(LED34-DO)") (class "Default")
      (node (ref "LED34") (pin "2-DOUT") (pinfunction "DO_2-DOUT") (pintype "output"))
      (node (ref "LED35") (pin "4-DIN") (pinfunction "DI_4-DIN") (pintype "input"))
    )
    (net (code "32") (name "Net-(LED35-DO)") (class "Default")
      (node (ref "LED35") (pin "2-DOUT") (pinfunction "DO_2-DOUT") (pintype "output"))
      (node (ref "LED36") (pin "4-DIN") (pinfunction "DI_4-DIN") (pintype "input"))
    )
    (net (code "33") (name "Net-(LED36-DO)") (class "Default")
      (node (ref "LED36") (pin "2-DOUT") (pinfunction "DO_2-DOUT") (pintype "output"))
      (node (ref "LED37") (pin "4-DIN") (pinfunction "DI_4-DIN") (pintype "input"))
    )
    (net (code "34") (name "Net-(LED37-DO)") (class "Default")
      (node (ref "LED37") (pin "2-DOUT") (pinfunction "DO_2-DOUT") (pintype "output"))
      (node (ref "LED38") (pin "4-DIN") (pinfunction "DI_4-DIN") (pintype "input"))
    )
    (net (code "35") (name "Net-(LED38-DO)") (class "Default")
      (node (ref "LED38") (pin "2-DOUT") (pinfunction "DO_2-DOUT") (pintype "output"))
      (node (ref "LED39") (pin "4-DIN") (pinfunction "DI_4-DIN") (pintype "input"))
    )
    (net (code "36") (name "Net-(LED39-DO)") (class "Default")
      (node (ref "LED39") (pin "2-DOUT") (pinfunction "DO_2-DOUT") (pintype "output"))
      (node (ref "S3") (pin "5") (pinfunction "2_5") (pintype "passive"))
      (node (ref "S4") (pin "4") (pinfunction "1_4") (pintype "passive"))
    )
    (net (code "37") (name "Net-(L_X1-DI)") (class "Default")
      (node (ref "L_X1") (pin "4-DIN") (pinfunction "DI_4-DIN") (pintype "input"))
      (node (ref "S2") (pin "11") (pinfunction "2_11") (pintype "passive"))
    )
    (net (code "38") (name "Net-(L_X1-DO)") (class "Default")
      (node (ref "L_X1") (pin "2-DOUT") (pinfunction "DO_2-DOUT") (pintype "output"))
      (node (ref "S1") (pin "20") (pinfunction "2_20") (pintype "passive"))
      (node (ref "S2") (pin "1") (pinfunction "1_1") (pintype "passive"))
    )
    (net (code "39") (name "Net-(L_X2-DI)") (class "Default")
      (node (ref "L_X2") (pin "4-DIN") (pinfunction "DI_4-DIN") (pintype "input"))
      (node (ref "S2") (pin "20") (pinfunction "2_20") (pintype "passive"))
    )
    (net (code "40") (name "Net-(L_X2-DO)") (class "Default")
      (node (ref "L_X2") (pin "2-DOUT") (pinfunction "DO_2-DOUT") (pintype "output"))
      (node (ref "S1") (pin "19") (pinfunction "2_19") (pintype "passive"))
      (node (ref "S2") (pin "2") (pinfunction "1_2") (pintype "passive"))
    )
    (net (code "41") (name "Net-(L_X3-DI)") (class "Default")
      (node (ref "L_X3") (pin "4-DIN") (pinfunction "DI_4-DIN") (pintype "input"))
      (node (ref "S2") (pin "19") (pinfunction "2_19") (pintype "passive"))
    )
    (net (code "42") (name "Net-(L_X3-DO)") (class "Default")
      (node (ref "L_X3") (pin "2-DOUT") (pinfunction "DO_2-DOUT") (pintype "output"))
      (node (ref "S1") (pin "18") (pinfunction "2_18") (pintype "passive"))
      (node (ref "S2") (pin "3") (pinfunction "1_3") (pintype "passive"))
    )
    (net (code "43") (name "Net-(L_X4-DI)") (class "Default")
      (node (ref "L_X4") (pin "4-DIN") (pinfunction "DI_4-DIN") (pintype "input"))
      (node (ref "S2") (pin "18") (pinfunction "2_18") (pintype "passive"))
    )
    (net (code "44") (name "Net-(L_X4-DO)") (class "Default")
      (node (ref "L_X4") (pin "2-DOUT") (pinfunction "DO_2-DOUT") (pintype "output"))
      (node (ref "S1") (pin "17") (pinfunction "2_17") (pintype "passive"))
      (node (ref "S2") (pin "4") (pinfunction "1_4") (pintype "passive"))
    )
    (net (code "45") (name "Net-(L_X5-DI)") (class "Default")
      (node (ref "L_X5") (pin "4-DIN") (pinfunction "DI_4-DIN") (pintype "input"))
      (node (ref "S2") (pin "17") (pinfunction "2_17") (pintype "passive"))
    )
    (net (code "46") (name "Net-(L_X5-DO)") (class "Default")
      (node (ref "L_X5") (pin "2-DOUT") (pinfunction "DO_2-DOUT") (pintype "output"))
      (node (ref "S1") (pin "16") (pinfunction "2_16") (pintype "passive"))
      (node (ref "S2") (pin "5") (pinfunction "1_5") (pintype "passive"))
    )
    (net (code "47") (name "Net-(L_X6-DI)") (class "Default")
      (node (ref "L_X6") (pin "4-DIN") (pinfunction "DI_4-DIN") (pintype "input"))
      (node (ref "S2") (pin "16") (pinfunction "2_16") (pintype "passive"))
    )
    (net (code "48") (name "Net-(L_X6-DO)") (class "Default")
      (node (ref "L_X6") (pin "2-DOUT") (pinfunction "DO_2-DOUT") (pintype "output"))
      (node (ref "S1") (pin "15") (pinfunction "2_15") (pintype "passive"))
      (node (ref "S2") (pin "6") (pinfunction "1_6") (pintype "passive"))
    )
    (net (code "49") (name "Net-(L_X7-DI)") (class "Default")
      (node (ref "L_X7") (pin "4-DIN") (pinfunction "DI_4-DIN") (pintype "input"))
      (node (ref "S2") (pin "15") (pinfunction "2_15") (pintype "passive"))
    )
    (net (code "50") (name "Net-(L_X7-DO)") (class "Default")
      (node (ref "L_X7") (pin "2-DOUT") (pinfunction "DO_2-DOUT") (pintype "output"))
      (node (ref "S1") (pin "14") (pinfunction "2_14") (pintype "passive"))
      (node (ref "S2") (pin "7") (pinfunction "1_7") (pintype "passive"))
    )
    (net (code "51") (name "Net-(L_X8-DI)") (class "Default")
      (node (ref "L_X8") (pin "4-DIN") (pinfunction "DI_4-DIN") (pintype "input"))
      (node (ref "S2") (pin "14") (pinfunction "2_14") (pintype "passive"))
    )
    (net (code "52") (name "Net-(L_X8-DO)") (class "Default")
      (node (ref "L_X8") (pin "2-DOUT") (pinfunction "DO_2-DOUT") (pintype "output"))
      (node (ref "S1") (pin "13") (pinfunction "2_13") (pintype "passive"))
      (node (ref "S2") (pin "8") (pinfunction "1_8") (pintype "passive"))
    )
    (net (code "53") (name "Net-(L_X9-DI)") (class "Default")
      (node (ref "L_X9") (pin "4-DIN") (pinfunction "DI_4-DIN") (pintype "input"))
      (node (ref "S2") (pin "13") (pinfunction "2_13") (pintype "passive"))
    )
    (net (code "54") (name "Net-(L_X9-DO)") (class "Default")
      (node (ref "L_X9") (pin "2-DOUT") (pinfunction "DO_2-DOUT") (pintype "output"))
      (node (ref "S1") (pin "12") (pinfunction "2_12") (pintype "passive"))
      (node (ref "S2") (pin "9") (pinfunction "1_9") (pintype "passive"))
    )
    (net (code "55") (name "Net-(S1B-1)") (class "Default")
      (node (ref "JP1") (pin "2") (pinfunction "2_2") (pintype "passive"))
      (node (ref "S1") (pin "1") (pinfunction "1_1") (pintype "passive"))
      (node (ref "S1") (pin "10") (pinfunction "1_10") (pintype "passive"))
      (node (ref "S1") (pin "2") (pinfunction "1_2") (pintype "passive"))
      (node (ref "S1") (pin "3") (pinfunction "1_3") (pintype "passive"))
      (node (ref "S1") (pin "4") (pinfunction "1_4") (pintype "passive"))
      (node (ref "S1") (pin "5") (pinfunction "1_5") (pintype "passive"))
      (node (ref "S1") (pin "6") (pinfunction "1_6") (pintype "passive"))
      (node (ref "S1") (pin "7") (pinfunction "1_7") (pintype "passive"))
      (node (ref "S1") (pin "8") (pinfunction "1_8") (pintype "passive"))
      (node (ref "S1") (pin "9") (pinfunction "1_9") (pintype "passive"))
      (node (ref "SV2") (pin "2") (pinfunction "2_2") (pintype "passive"))
    )
    (net (code "56") (name "Net-(S1B-2)") (class "Default")
      (node (ref "S1") (pin "11") (pinfunction "2_11") (pintype "passive"))
      (node (ref "S2") (pin "10") (pinfunction "1_10") (pintype "passive"))
      (node (ref "S3") (pin "1") (pinfunction "1_1") (pintype "passive"))
      (node (ref "S3") (pin "2") (pinfunction "1_2") (pintype "passive"))
      (node (ref "S3") (pin "3") (pinfunction "1_3") (pintype "passive"))
      (node (ref "S3") (pin "4") (pinfunction "1_4") (pintype "passive"))
    )
    (net (code "57") (name "Net-(S3A-2)") (class "Default")
      (node (ref "S3") (pin "8") (pinfunction "2_8") (pintype "passive"))
      (node (ref "S4") (pin "1") (pinfunction "1_1") (pintype "passive"))
      (node (ref "SV1") (pin "2") (pinfunction "2_2") (pintype "passive"))
    )
    (net (code "58") (name "unconnected-(S2J-2-Pad12)") (class "Default")
      (node (ref "S2") (pin "12") (pinfunction "2_12") (pintype "passive"))
    )
    (net (code "59") (name "unconnected-(S4D-2-Pad5)") (class "Default")
      (node (ref "S4") (pin "5") (pinfunction "2_5") (pintype "passive"))
    )
    (net (code "60") (name "unconnected-(SV1-Pad6)") (class "Default")
      (node (ref "SV1") (pin "6") (pinfunction "6_6") (pintype "passive"))
    )
    (net (code "61") (name "unconnected-(SV2-Pad6)") (class "Default")
      (node (ref "SV2") (pin "6") (pinfunction "6_6") (pintype "passive"))
    )
  )
)
